# MoteinoR5USB-LP_fet.net
KiCad netlist of a schematic drawn in EAGLE
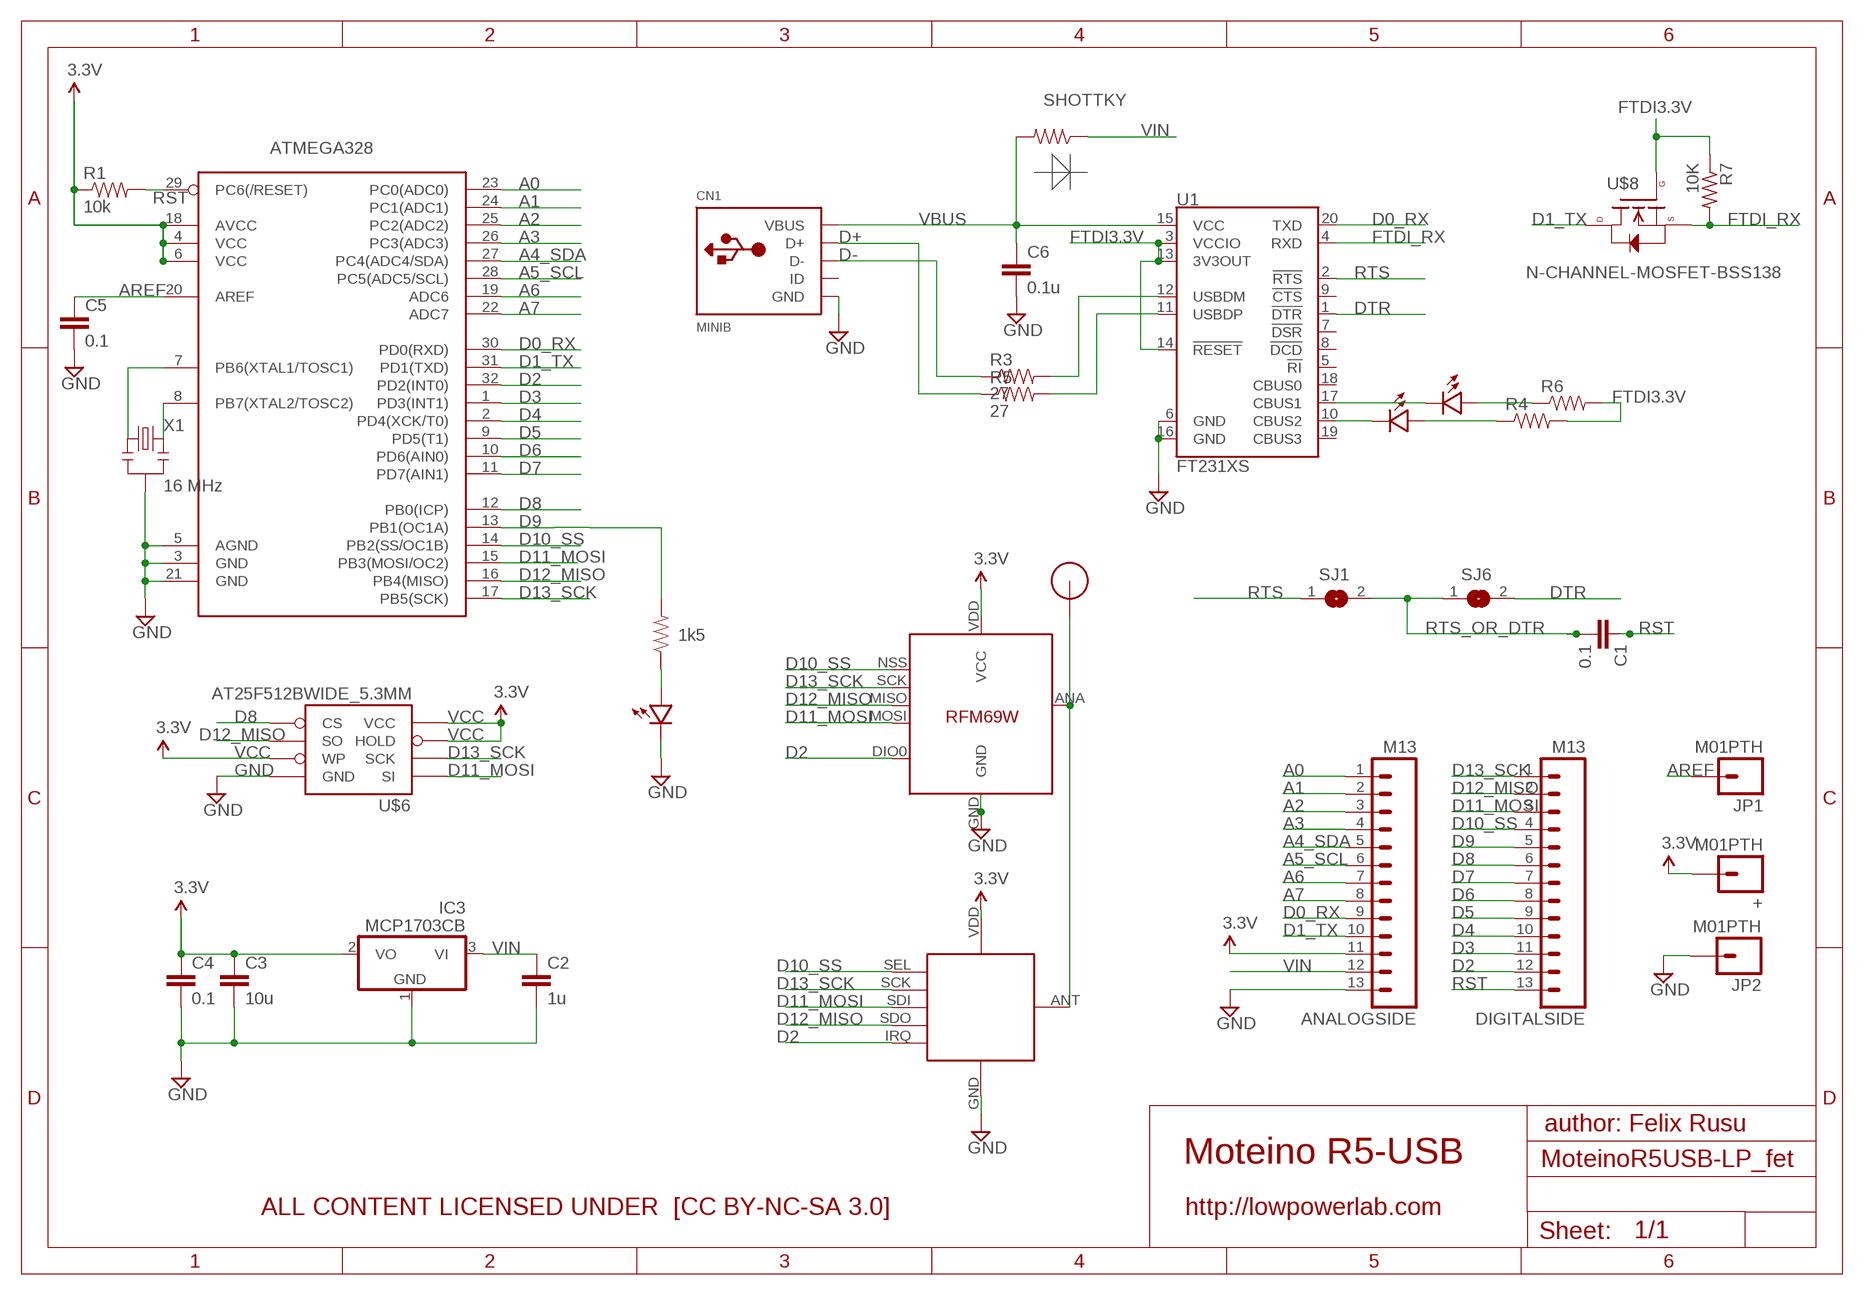
[diagram p0: schematic, sheet 1]

(export (version "E")
  (design (tool "Eeschema 10.0.6"))
  (components
    (comp (ref "+")
      (value "M01PTH")
      (footprint "eagle-import:1X01")
      (libsource (lib "eagle-import") (part "M01PTH"))
    )
    (comp (ref "ANALOGSIDE")
      (value "M13")
      (footprint "eagle-import:1X13")
      (libsource (lib "eagle-import") (part "M13"))
    )
    (comp (ref "ATMEGA328")
      (value "ATMega-328")
      (footprint "eagle-import:TQFP32-08")
      (libsource (lib "eagle-import") (part "ATMEGA168/328TQFP32"))
    )
    (comp (ref "C1")
      (value "0.1")
      (footprint "eagle-import:0603-CAP")
      (libsource (lib "eagle-import") (part "CAP0603-CAP"))
    )
    (comp (ref "C2")
      (value "1u")
      (footprint "eagle-import:0603-CAP")
      (libsource (lib "eagle-import") (part "CAP0603-CAP"))
    )
    (comp (ref "C3")
      (value "10u")
      (footprint "eagle-import:0805-CAP")
      (libsource (lib "eagle-import") (part "CAP0805-CAP"))
    )
    (comp (ref "C4")
      (value "0.1")
      (footprint "eagle-import:0603-CAP")
      (libsource (lib "eagle-import") (part "CAP0603-CAP"))
    )
    (comp (ref "C5")
      (value "0.1")
      (footprint "eagle-import:0603-CAP")
      (libsource (lib "eagle-import") (part "CAP0603-CAP"))
    )
    (comp (ref "C6")
      (value "0.1u")
      (footprint "eagle-import:0603-CAP")
      (libsource (lib "eagle-import") (part "CAP0603-CAP"))
    )
    (comp (ref "CN1")
      (value "MINIB")
      (footprint "eagle-import:USB-MINIB")
      (libsource (lib "eagle-import") (part "USBMINIB"))
    )
    (comp (ref "D")
      (value "SHOTTKY")
      (footprint "eagle-import:0603-RES")
      (libsource (lib "eagle-import") (part "RESISTOR0603-RES"))
    )
    (comp (ref "DIGITALSIDE")
      (value "M13")
      (footprint "eagle-import:1X13")
      (libsource (lib "eagle-import") (part "M13"))
    )
    (comp (ref "IC3")
      (value "MCP1703CB")
      (footprint "eagle-import:SOT23")
      (libsource (lib "eagle-import") (part "MCP1703CB"))
    )
    (comp (ref "JP1")
      (value "M01PTH")
      (footprint "eagle-import:1X01")
      (libsource (lib "eagle-import") (part "M01PTH"))
    )
    (comp (ref "JP2")
      (value "M01PTH")
      (footprint "eagle-import:1X01")
      (libsource (lib "eagle-import") (part "M01PTH"))
    )
    (comp (ref "R1")
      (value "10k")
      (footprint "eagle-import:0603-RES")
      (libsource (lib "eagle-import") (part "RESISTOR0603-RES"))
    )
    (comp (ref "R2")
      (value "1k5")
      (footprint "eagle-import:0603-RES")
      (libsource (lib "eagle-import") (part "RESISTOR0603-RES"))
    )
    (comp (ref "R3")
      (value "27")
      (footprint "eagle-import:0603-RES")
      (libsource (lib "eagle-import") (part "RESISTOR0603-RES"))
    )
    (comp (ref "R4")
      (value "RESISTOR0603-RES")
      (footprint "eagle-import:0603-RES")
      (libsource (lib "eagle-import") (part "RESISTOR0603-RES"))
    )
    (comp (ref "R5")
      (value "27")
      (footprint "eagle-import:0603-RES")
      (libsource (lib "eagle-import") (part "RESISTOR0603-RES"))
    )
    (comp (ref "R6")
      (value "RESISTOR0603-RES")
      (footprint "eagle-import:0603-RES")
      (libsource (lib "eagle-import") (part "RESISTOR0603-RES"))
    )
    (comp (ref "R7")
      (value "10K")
      (footprint "eagle-import:R0805")
      (libsource (lib "eagle-import") (part "R-US_R0805"))
    )
    (comp (ref "RFM12B")
      (value "RFM12B_MINPADS")
      (footprint "eagle-import:RFM12B-MINPADS")
      (libsource (lib "eagle-import") (part "RFM12B_MINPADS"))
    )
    (comp (ref "SJ1")
      (value "JUMPER")
      (footprint "eagle-import:SJW")
      (libsource (lib "eagle-import") (part "JUMPER"))
    )
    (comp (ref "SJ6")
      (value "JUMPER")
      (footprint "eagle-import:SJW")
      (libsource (lib "eagle-import") (part "JUMPER"))
    )
    (comp (ref "U$1")
      (value "RFM12B_ANTENNA")
      (footprint "eagle-import:RFM12B-ANTENNA")
      (libsource (lib "eagle-import") (part "RFM12B_ANTENNA"))
    )
    (comp (ref "U$2")
      (value "LED0603")
      (footprint "eagle-import:0603-LED")
      (libsource (lib "eagle-import") (part "LED0603"))
    )
    (comp (ref "U$4")
      (value "LED0603")
      (footprint "eagle-import:0603-LED")
      (libsource (lib "eagle-import") (part "LED0603"))
    )
    (comp (ref "U$5")
      (value "RFM69")
      (footprint "eagle-import:RFM69W-MINPADS")
      (libsource (lib "eagle-import") (part "RFM69"))
    )
    (comp (ref "U$6")
      (value "AT25F512BWIDE_5.3MM")
      (footprint "eagle-import:SO08WIDE")
      (libsource (lib "eagle-import") (part "AT25F512BWIDE_5.3MM"))
    )
    (comp (ref "U$7")
      (value "LED0603")
      (footprint "eagle-import:0603-LED")
      (libsource (lib "eagle-import") (part "LED0603"))
    )
    (comp (ref "U$8")
      (value "N-CHANNEL-MOSFET-BSS138")
      (footprint "eagle-import:SOT23-3")
      (libsource (lib "eagle-import") (part "N-CHANNEL-MOSFET-BSS138"))
    )
    (comp (ref "U1")
      (value "FT231XS")
      (footprint "eagle-import:SSOP20_L")
      (libsource (lib "eagle-import") (part "FT231XS"))
    )
    (comp (ref "X1")
      (value "16 MHz")
      (footprint "eagle-import:RESONATOR-SMD")
      (libsource (lib "eagle-import") (part "RESONATORSMD"))
    )
  )
  (nets
    (net (code "1") (name "/A0") (class "Default")
      (node (ref "ANALOGSIDE") (pin "1") (pinfunction "1_1") (pintype "passive"))
      (node (ref "ATMEGA328") (pin "23") (pinfunction "PC0(ADC0)_23") (pintype "bidirectional"))
    )
    (net (code "2") (name "/A1") (class "Default")
      (node (ref "ANALOGSIDE") (pin "2") (pinfunction "2_2") (pintype "passive"))
      (node (ref "ATMEGA328") (pin "24") (pinfunction "PC1(ADC1)_24") (pintype "bidirectional"))
    )
    (net (code "3") (name "/A2") (class "Default")
      (node (ref "ANALOGSIDE") (pin "3") (pinfunction "3_3") (pintype "passive"))
      (node (ref "ATMEGA328") (pin "25") (pinfunction "PC2(ADC2)_25") (pintype "bidirectional"))
    )
    (net (code "4") (name "/A3") (class "Default")
      (node (ref "ANALOGSIDE") (pin "4") (pinfunction "4_4") (pintype "passive"))
      (node (ref "ATMEGA328") (pin "26") (pinfunction "PC3(ADC3)_26") (pintype "bidirectional"))
    )
    (net (code "5") (name "/A4_SDA") (class "Default")
      (node (ref "ANALOGSIDE") (pin "5") (pinfunction "5_5") (pintype "passive"))
      (node (ref "ATMEGA328") (pin "27") (pinfunction "PC4(ADC4/SDA)_27") (pintype "bidirectional"))
    )
    (net (code "6") (name "/A5_SCL") (class "Default")
      (node (ref "ANALOGSIDE") (pin "6") (pinfunction "6_6") (pintype "passive"))
      (node (ref "ATMEGA328") (pin "28") (pinfunction "PC5(ADC5/SCL)_28") (pintype "bidirectional"))
    )
    (net (code "7") (name "/A6") (class "Default")
      (node (ref "ANALOGSIDE") (pin "7") (pinfunction "7_7") (pintype "passive"))
      (node (ref "ATMEGA328") (pin "19") (pinfunction "ADC6_19") (pintype "bidirectional"))
    )
    (net (code "8") (name "/A7") (class "Default")
      (node (ref "ANALOGSIDE") (pin "8") (pinfunction "8_8") (pintype "passive"))
      (node (ref "ATMEGA328") (pin "22") (pinfunction "ADC7_22") (pintype "bidirectional"))
    )
    (net (code "9") (name "/AREF") (class "Default")
      (node (ref "ATMEGA328") (pin "20") (pinfunction "AREF_20") (pintype "bidirectional"))
      (node (ref "C5") (pin "1") (pinfunction "1_1") (pintype "passive"))
      (node (ref "JP1") (pin "1") (pinfunction "1_1") (pintype "passive"))
    )
    (net (code "10") (name "/D+") (class "Default")
      (node (ref "CN1") (pin "D+") (pinfunction "D+_D+") (pintype "bidirectional"))
      (node (ref "R5") (pin "1") (pinfunction "1_1") (pintype "passive"))
    )
    (net (code "11") (name "/D-") (class "Default")
      (node (ref "CN1") (pin "D-") (pinfunction "D-_D-") (pintype "bidirectional"))
      (node (ref "R3") (pin "1") (pinfunction "1_1") (pintype "passive"))
    )
    (net (code "12") (name "/D0_RX") (class "Default")
      (node (ref "ANALOGSIDE") (pin "9") (pinfunction "9_9") (pintype "passive"))
      (node (ref "ATMEGA328") (pin "30") (pinfunction "PD0(RXD)_30") (pintype "bidirectional"))
      (node (ref "U1") (pin "20") (pinfunction "TXD_20") (pintype "bidirectional"))
    )
    (net (code "13") (name "/D1_TX") (class "Default")
      (node (ref "ANALOGSIDE") (pin "10") (pinfunction "10_10") (pintype "passive"))
      (node (ref "ATMEGA328") (pin "31") (pinfunction "PD1(TXD)_31") (pintype "bidirectional"))
      (node (ref "U$8") (pin "3") (pinfunction "D_3") (pintype "passive"))
    )
    (net (code "14") (name "/D2") (class "Default")
      (node (ref "ATMEGA328") (pin "32") (pinfunction "PD2(INT0)_32") (pintype "bidirectional"))
      (node (ref "DIGITALSIDE") (pin "12") (pinfunction "12_12") (pintype "passive"))
      (node (ref "RFM12B") (pin "IRQ") (pinfunction "IRQ_IRQ") (pintype "bidirectional"))
      (node (ref "U$5") (pin "DIO0") (pinfunction "DIO0_DIO0") (pintype "open_collector"))
    )
    (net (code "15") (name "/D3") (class "Default")
      (node (ref "ATMEGA328") (pin "1") (pinfunction "PD3(INT1)_1") (pintype "bidirectional"))
      (node (ref "DIGITALSIDE") (pin "11") (pinfunction "11_11") (pintype "passive"))
    )
    (net (code "16") (name "/D4") (class "Default")
      (node (ref "ATMEGA328") (pin "2") (pinfunction "PD4(XCK/T0)_2") (pintype "bidirectional"))
      (node (ref "DIGITALSIDE") (pin "10") (pinfunction "10_10") (pintype "passive"))
    )
    (net (code "17") (name "/D5") (class "Default")
      (node (ref "ATMEGA328") (pin "9") (pinfunction "PD5(T1)_9") (pintype "bidirectional"))
      (node (ref "DIGITALSIDE") (pin "9") (pinfunction "9_9") (pintype "passive"))
    )
    (net (code "18") (name "/D6") (class "Default")
      (node (ref "ATMEGA328") (pin "10") (pinfunction "PD6(AIN0)_10") (pintype "bidirectional"))
      (node (ref "DIGITALSIDE") (pin "8") (pinfunction "8_8") (pintype "passive"))
    )
    (net (code "19") (name "/D7") (class "Default")
      (node (ref "ATMEGA328") (pin "11") (pinfunction "PD7(AIN1)_11") (pintype "bidirectional"))
      (node (ref "DIGITALSIDE") (pin "7") (pinfunction "7_7") (pintype "passive"))
    )
    (net (code "20") (name "/D8") (class "Default")
      (node (ref "ATMEGA328") (pin "12") (pinfunction "PB0(ICP)_12") (pintype "bidirectional"))
      (node (ref "DIGITALSIDE") (pin "6") (pinfunction "6_6") (pintype "passive"))
      (node (ref "U$6") (pin "1") (pinfunction "CS_1") (pintype "bidirectional"))
    )
    (net (code "21") (name "/D9") (class "Default")
      (node (ref "ATMEGA328") (pin "13") (pinfunction "PB1(OC1A)_13") (pintype "bidirectional"))
      (node (ref "DIGITALSIDE") (pin "5") (pinfunction "5_5") (pintype "passive"))
      (node (ref "R2") (pin "2") (pinfunction "2_2") (pintype "passive"))
    )
    (net (code "22") (name "/D10_SS") (class "Default")
      (node (ref "ATMEGA328") (pin "14") (pinfunction "PB2(SS/OC1B)_14") (pintype "bidirectional"))
      (node (ref "DIGITALSIDE") (pin "4") (pinfunction "4_4") (pintype "passive"))
      (node (ref "RFM12B") (pin "SEL") (pinfunction "SEL_SEL") (pintype "bidirectional"))
      (node (ref "U$5") (pin "NSS") (pinfunction "SEL_NSS") (pintype "input"))
    )
    (net (code "23") (name "/D11_MOSI") (class "Default")
      (node (ref "ATMEGA328") (pin "15") (pinfunction "PB3(MOSI/OC2)_15") (pintype "bidirectional"))
      (node (ref "DIGITALSIDE") (pin "3") (pinfunction "3_3") (pintype "passive"))
      (node (ref "RFM12B") (pin "SDI") (pinfunction "SDI/MOSI_SDI") (pintype "bidirectional"))
      (node (ref "U$5") (pin "MOSI") (pinfunction "MOSI_MOSI") (pintype "output"))
      (node (ref "U$6") (pin "5") (pinfunction "SI_5") (pintype "bidirectional"))
    )
    (net (code "24") (name "/D12_MISO") (class "Default")
      (node (ref "ATMEGA328") (pin "16") (pinfunction "PB4(MISO)_16") (pintype "bidirectional"))
      (node (ref "DIGITALSIDE") (pin "2") (pinfunction "2_2") (pintype "passive"))
      (node (ref "RFM12B") (pin "SDO") (pinfunction "SDO/MISO_SDO") (pintype "bidirectional"))
      (node (ref "U$5") (pin "MISO") (pinfunction "MISO_MISO") (pintype "input"))
      (node (ref "U$6") (pin "2") (pinfunction "SO_2") (pintype "bidirectional"))
    )
    (net (code "25") (name "/D13_SCK") (class "Default")
      (node (ref "ATMEGA328") (pin "17") (pinfunction "PB5(SCK)_17") (pintype "bidirectional"))
      (node (ref "DIGITALSIDE") (pin "1") (pinfunction "1_1") (pintype "passive"))
      (node (ref "RFM12B") (pin "SCK") (pinfunction "SCK_SCK") (pintype "bidirectional"))
      (node (ref "U$5") (pin "SCK") (pinfunction "SCK_SCK") (pintype "input"))
      (node (ref "U$6") (pin "6") (pinfunction "SCK_6") (pintype "bidirectional"))
    )
    (net (code "26") (name "/DTR") (class "Default")
      (node (ref "SJ6") (pin "2") (pinfunction "2_2") (pintype "passive"))
      (node (ref "U1") (pin "1") (pinfunction "~{DTR}_1") (pintype "bidirectional"))
    )
    (net (code "27") (name "/FTDI3.3V") (class "Default")
      (node (ref "R4") (pin "2") (pinfunction "2_2") (pintype "passive"))
      (node (ref "R6") (pin "2") (pinfunction "2_2") (pintype "passive"))
      (node (ref "R7") (pin "1") (pinfunction "1_1") (pintype "passive"))
      (node (ref "U$8") (pin "1") (pinfunction "G_1") (pintype "passive"))
      (node (ref "U1") (pin "13") (pinfunction "3V3OUT_13") (pintype "bidirectional"))
      (node (ref "U1") (pin "14") (pinfunction "~{RESET}_14") (pintype "bidirectional"))
      (node (ref "U1") (pin "3") (pinfunction "VCCIO_3") (pintype "bidirectional"))
    )
    (net (code "28") (name "/FTDI_RX") (class "Default")
      (node (ref "R7") (pin "2") (pinfunction "2_2") (pintype "passive"))
      (node (ref "U$8") (pin "2") (pinfunction "S_2") (pintype "passive"))
      (node (ref "U1") (pin "4") (pinfunction "RXD_4") (pintype "bidirectional"))
    )
    (net (code "29") (name "/RST") (class "Default")
      (node (ref "ATMEGA328") (pin "29") (pinfunction "PC6(/RESET)_29") (pintype "bidirectional"))
      (node (ref "C1") (pin "1") (pinfunction "1_1") (pintype "passive"))
      (node (ref "DIGITALSIDE") (pin "13") (pinfunction "13_13") (pintype "passive"))
      (node (ref "R1") (pin "2") (pinfunction "2_2") (pintype "passive"))
    )
    (net (code "30") (name "/RTS") (class "Default")
      (node (ref "SJ1") (pin "1") (pinfunction "1_1") (pintype "passive"))
      (node (ref "U1") (pin "2") (pinfunction "~{RTS}_2") (pintype "bidirectional"))
    )
    (net (code "31") (name "/RTS_OR_DTR") (class "Default")
      (node (ref "C1") (pin "2") (pinfunction "2_2") (pintype "passive"))
      (node (ref "SJ1") (pin "2") (pinfunction "2_2") (pintype "passive"))
      (node (ref "SJ6") (pin "1") (pinfunction "1_1") (pintype "passive"))
    )
    (net (code "32") (name "/VBUS") (class "Default")
      (node (ref "C6") (pin "1") (pinfunction "1_1") (pintype "passive"))
      (node (ref "CN1") (pin "VBUS") (pinfunction "VBUS_VBUS") (pintype "power_in"))
      (node (ref "D") (pin "2") (pinfunction "2_2") (pintype "passive"))
      (node (ref "U1") (pin "15") (pinfunction "VCC_15") (pintype "bidirectional"))
    )
    (net (code "33") (name "/VIN") (class "Default")
      (node (ref "ANALOGSIDE") (pin "12") (pinfunction "12_12") (pintype "passive"))
      (node (ref "C2") (pin "1") (pinfunction "1_1") (pintype "passive"))
      (node (ref "D") (pin "1") (pinfunction "1_1") (pintype "passive"))
      (node (ref "IC3") (pin "3") (pinfunction "VI_3") (pintype "input"))
    )
    (net (code "34") (name "3.3V") (class "Default")
      (node (ref "+") (pin "1") (pinfunction "1_1") (pintype "passive"))
      (node (ref "ANALOGSIDE") (pin "11") (pinfunction "11_11") (pintype "passive"))
      (node (ref "ATMEGA328") (pin "18") (pinfunction "AVCC_18") (pintype "bidirectional"))
      (node (ref "ATMEGA328") (pin "4") (pinfunction "VCC_4") (pintype "bidirectional"))
      (node (ref "ATMEGA328") (pin "6") (pinfunction "VCC_6") (pintype "bidirectional"))
      (node (ref "C3") (pin "1") (pinfunction "1_1") (pintype "passive"))
      (node (ref "C4") (pin "1") (pinfunction "1_1") (pintype "passive"))
      (node (ref "IC3") (pin "2") (pinfunction "VO_2") (pintype "passive"))
      (node (ref "R1") (pin "1") (pinfunction "1_1") (pintype "passive"))
      (node (ref "RFM12B") (pin "VDD") (pinfunction "VDD_VDD") (pintype "bidirectional"))
      (node (ref "U$5") (pin "VDD") (pinfunction "VCC_VDD") (pintype "power_in"))
      (node (ref "U$6") (pin "3") (pinfunction "WP_3") (pintype "bidirectional"))
      (node (ref "U$6") (pin "7") (pinfunction "HOLD_7") (pintype "bidirectional"))
      (node (ref "U$6") (pin "8") (pinfunction "VCC_8") (pintype "bidirectional"))
    )
    (net (code "35") (name "GND") (class "Default")
      (node (ref "ANALOGSIDE") (pin "13") (pinfunction "13_13") (pintype "passive"))
      (node (ref "ATMEGA328") (pin "21") (pinfunction "GND_21") (pintype "bidirectional"))
      (node (ref "ATMEGA328") (pin "3") (pinfunction "GND_3") (pintype "bidirectional"))
      (node (ref "ATMEGA328") (pin "5") (pinfunction "AGND_5") (pintype "bidirectional"))
      (node (ref "C2") (pin "2") (pinfunction "2_2") (pintype "passive"))
      (node (ref "C3") (pin "2") (pinfunction "2_2") (pintype "passive"))
      (node (ref "C4") (pin "2") (pinfunction "2_2") (pintype "passive"))
      (node (ref "C5") (pin "2") (pinfunction "2_2") (pintype "passive"))
      (node (ref "C6") (pin "2") (pinfunction "2_2") (pintype "passive"))
      (node (ref "CN1") (pin "GND") (pinfunction "GND_GND") (pintype "power_in"))
      (node (ref "IC3") (pin "1") (pinfunction "GND_1") (pintype "passive"))
      (node (ref "JP2") (pin "1") (pinfunction "1_1") (pintype "passive"))
      (node (ref "RFM12B") (pin "GND") (pinfunction "GND_GND") (pintype "bidirectional"))
      (node (ref "U$2") (pin "MINUS") (pinfunction "MINUS_MINUS") (pintype "passive"))
      (node (ref "U$5") (pin "GND") (pinfunction "GND_GND") (pintype "power_in"))
      (node (ref "U$6") (pin "4") (pinfunction "GND_4") (pintype "bidirectional"))
      (node (ref "U1") (pin "16") (pinfunction "GND_16") (pintype "bidirectional"))
      (node (ref "U1") (pin "6") (pinfunction "GND_6") (pintype "bidirectional"))
      (node (ref "X1") (pin "2") (pinfunction "2_2") (pintype "passive"))
    )
    (net (code "36") (name "Net-(ATMEGA328-PB6(XTAL1{slash}TOSC1))") (class "Default")
      (node (ref "ATMEGA328") (pin "7") (pinfunction "PB6(XTAL1/TOSC1)_7") (pintype "bidirectional"))
      (node (ref "X1") (pin "1") (pinfunction "1_1") (pintype "passive"))
    )
    (net (code "37") (name "Net-(ATMEGA328-PB7(XTAL2{slash}TOSC2))") (class "Default")
      (node (ref "ATMEGA328") (pin "8") (pinfunction "PB7(XTAL2/TOSC2)_8") (pintype "bidirectional"))
      (node (ref "X1") (pin "3") (pinfunction "3_3") (pintype "passive"))
    )
    (net (code "38") (name "Net-(R2-Pad1)") (class "Default")
      (node (ref "R2") (pin "1") (pinfunction "1_1") (pintype "passive"))
      (node (ref "U$2") (pin "PLUS") (pinfunction "PLUS_PLUS") (pintype "passive"))
    )
    (net (code "39") (name "Net-(R4-Pad1)") (class "Default")
      (node (ref "R4") (pin "1") (pinfunction "1_1") (pintype "passive"))
      (node (ref "U$7") (pin "PLUS") (pinfunction "PLUS_PLUS") (pintype "passive"))
    )
    (net (code "40") (name "Net-(R6-Pad1)") (class "Default")
      (node (ref "R6") (pin "1") (pinfunction "1_1") (pintype "passive"))
      (node (ref "U$4") (pin "PLUS") (pinfunction "PLUS_PLUS") (pintype "passive"))
    )
    (net (code "41") (name "Net-(U$1-1)") (class "Default")
      (node (ref "RFM12B") (pin "ANT") (pinfunction "ANT_ANT") (pintype "bidirectional"))
      (node (ref "U$1") (pin "P$1") (pinfunction "1_P$1") (pintype "bidirectional"))
      (node (ref "U$5") (pin "ANA") (pinfunction "ANT_ANA") (pintype "passive"))
    )
    (net (code "42") (name "Net-(U1-CBUS1)") (class "Default")
      (node (ref "U$4") (pin "MINUS") (pinfunction "MINUS_MINUS") (pintype "passive"))
      (node (ref "U1") (pin "17") (pinfunction "CBUS1_17") (pintype "bidirectional"))
    )
    (net (code "43") (name "Net-(U1-CBUS2)") (class "Default")
      (node (ref "U$7") (pin "MINUS") (pinfunction "MINUS_MINUS") (pintype "passive"))
      (node (ref "U1") (pin "10") (pinfunction "CBUS2_10") (pintype "bidirectional"))
    )
    (net (code "44") (name "Net-(U1-USBDM)") (class "Default")
      (node (ref "R3") (pin "2") (pinfunction "2_2") (pintype "passive"))
      (node (ref "U1") (pin "12") (pinfunction "USBDM_12") (pintype "bidirectional"))
    )
    (net (code "45") (name "Net-(U1-USBDP)") (class "Default")
      (node (ref "R5") (pin "2") (pinfunction "2_2") (pintype "passive"))
      (node (ref "U1") (pin "11") (pinfunction "USBDP_11") (pintype "bidirectional"))
    )
    (net (code "46") (name "unconnected-(CN1-PadID)") (class "Default")
      (node (ref "CN1") (pin "ID") (pinfunction "ID_ID") (pintype "bidirectional"))
    )
    (net (code "47") (name "unconnected-(U1-CBUS0-Pad18)") (class "Default")
      (node (ref "U1") (pin "18") (pinfunction "CBUS0_18") (pintype "bidirectional"))
    )
    (net (code "48") (name "unconnected-(U1-CBUS3-Pad19)") (class "Default")
      (node (ref "U1") (pin "19") (pinfunction "CBUS3_19") (pintype "bidirectional"))
    )
    (net (code "49") (name "unconnected-(U1-~{CTS}-Pad9)") (class "Default")
      (node (ref "U1") (pin "9") (pinfunction "~{CTS}_9") (pintype "bidirectional"))
    )
    (net (code "50") (name "unconnected-(U1-~{DCD}-Pad8)") (class "Default")
      (node (ref "U1") (pin "8") (pinfunction "~{DCD}_8") (pintype "bidirectional"))
    )
    (net (code "51") (name "unconnected-(U1-~{DSR}-Pad7)") (class "Default")
      (node (ref "U1") (pin "7") (pinfunction "~{DSR}_7") (pintype "bidirectional"))
    )
    (net (code "52") (name "unconnected-(U1-~{RI}-Pad5)") (class "Default")
      (node (ref "U1") (pin "5") (pinfunction "~{RI}_5") (pintype "bidirectional"))
    )
  )
)
